# Supply.net
KiCad netlist of a schematic drawn in Altium Designer
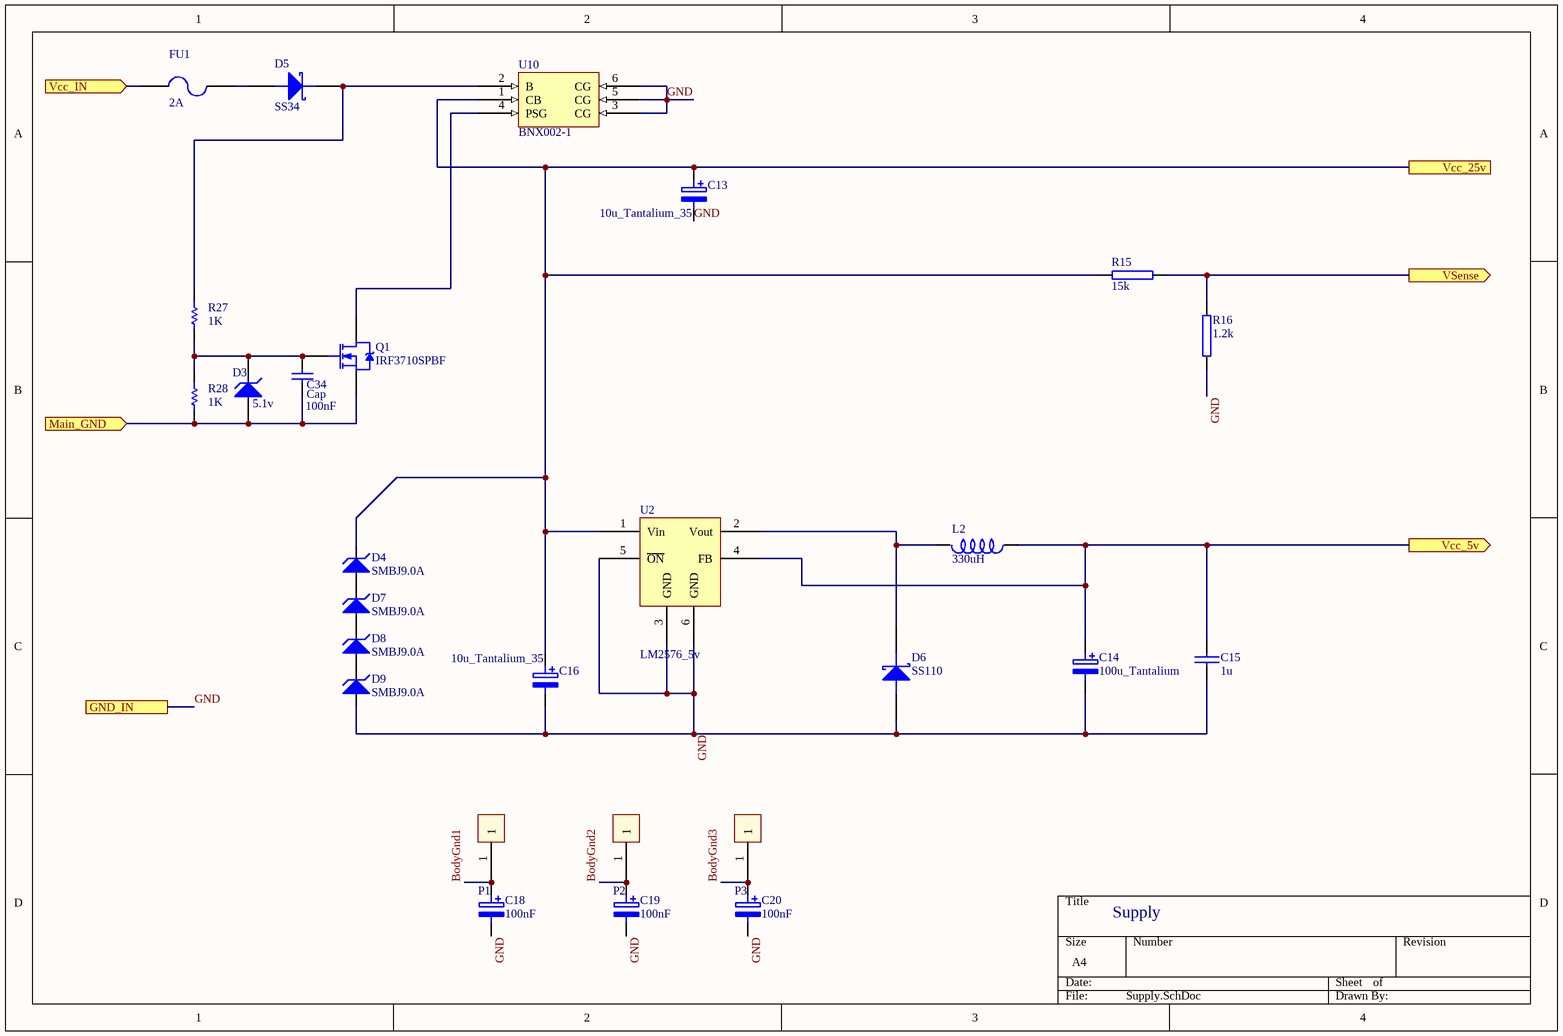
[diagram p0: Supply.SchDoc]

(export (version "E")
  (design (tool "Eeschema 10.0.6"))
  (components
    (comp (ref "C13")
      (value "10u_Tantalium_35")
      (footprint "Tantalum_9545")
      (libsource (lib "Sch_Lib_24") (part "CAP_ELECTRO"))
    )
    (comp (ref "C14")
      (value "100u_Tantalium")
      (footprint "Tantalum_9545")
      (libsource (lib "Miscellaneous Devices") (part "CAP_ELECTRO"))
    )
    (comp (ref "C15")
      (value "1u")
      (footprint "0805")
      (description "Capacitor")
      (libsource (lib "Sch_Lib_24") (part "CAP"))
    )
    (comp (ref "C16")
      (value "10u_Tantalium_35")
      (footprint "Tantalum_9545")
      (libsource (lib "Miscellaneous Devices") (part "CAP_ELECTRO"))
    )
    (comp (ref "C18")
      (value "100nF")
      (footprint "1206_SMD")
      (libsource (lib "Miscellaneous Devices") (part "CAP_ELECTRO"))
    )
    (comp (ref "C19")
      (value "100nF")
      (footprint "1206_SMD")
      (libsource (lib "Miscellaneous Devices") (part "CAP_ELECTRO"))
    )
    (comp (ref "C20")
      (value "100nF")
      (footprint "1206_SMD")
      (libsource (lib "Miscellaneous Devices") (part "CAP_ELECTRO"))
    )
    (comp (ref "C34")
      (value "Cap")
      (footprint "1206_SMD")
      (description "Capacitor")
      (fields (field (name "ALTIUM_VALUE") "100nF") (field (name "PUBLISHER") "Altium Limited"))
      (libsource (lib "Miscellaneous Devices") (part "Cap"))
    )
    (comp (ref "D3")
      (value "5.1v")
      (footprint "diode zener_smd")
      (description "Zener Diode")
      (fields (field (name "PUBLISHER") "Altium Limited"))
      (libsource (lib "Miscellaneous Devices") (part "D Zener"))
    )
    (comp (ref "D4") (value "SMBJ9.0A") (footprint "SMB") (libsource (lib "Sch_Lib_25") (part "ZENER")))
    (comp (ref "D5")
      (value "SS34")
      (footprint "SMC")
      (libsource (lib "Miscellaneous Devices") (part "DIODE_SCH"))
    )
    (comp (ref "D6") (value "SS110") (footprint "SMA") (libsource (lib "Sch_Lib_24") (part "DIODE_SCH")))
    (comp (ref "D7") (value "SMBJ9.0A") (footprint "SMB") (libsource (lib "Sch_Lib_25") (part "ZENER")))
    (comp (ref "D8") (value "SMBJ9.0A") (footprint "SMB") (libsource (lib "Sch_Lib_25") (part "ZENER")))
    (comp (ref "D9") (value "SMBJ9.0A") (footprint "SMB") (libsource (lib "Sch_Lib_25") (part "ZENER")))
    (comp (ref "FU1")
      (value "2A")
      (footprint "7227")
      (description "Fuse")
      (libsource (lib "Sch_Lib_24") (part "FUSE2"))
    )
    (comp (ref "L2")
      (value "330uH")
      (footprint "inductor_12.3*12.3")
      (libsource (lib "Miscellaneous Devices") (part "INDUCTOR"))
    )
    (comp (ref "P1") (value "head1") (footprint "PAD") (libsource (lib "CustomLib_Ver01") (part "head1")))
    (comp (ref "P2") (value "head1") (footprint "PAD") (libsource (lib "CustomLib_Ver01") (part "head1")))
    (comp (ref "P3") (value "head1") (footprint "PAD") (libsource (lib "CustomLib_Ver01") (part "head1")))
    (comp (ref "Q1")
      (value "IRF3710SPBF")
      (footprint "D2PAK")
      (description "N-Channel Power MOSFET")
      (fields (field (name "PUBLISHER") "Altium Limited"))
      (libsource (lib "Miscellaneous Devices") (part "NMOS-2"))
    )
    (comp (ref "R15") (value "15k") (footprint "1206_SMD") (libsource (lib "Sch_Lib_24") (part "RES2")))
    (comp (ref "R16") (value "1.2k") (footprint "1206_SMD") (libsource (lib "Sch_Lib_24") (part "RES2")))
    (comp (ref "R27")
      (value "1K")
      (footprint "0805_smd")
      (description "Resistor")
      (fields (field (name "Comment") "Res1") (field (name "PUBLISHER") "Altium Limited"))
      (libsource (lib "Miscellaneous Devices") (part "Res1"))
    )
    (comp (ref "R28")
      (value "1K")
      (footprint "0805")
      (description "Resistor")
      (fields (field (name "Comment") "Res1") (field (name "PUBLISHER") "Altium Limited"))
      (libsource (lib "Miscellaneous Devices") (part "Res1"))
    )
    (comp (ref "U2")
      (value "LM2576_5v")
      (footprint "TO263-5L")
      (libsource (lib "CustomLib_Ver01") (part "LM2576_5v"))
    )
    (comp (ref "U10")
      (value "BNX002-1")
      (footprint "BNX002-1")
      (description "EMI FILTERS")
      (libsource (lib "CustomLib_Ver01") (part "BNX002-1"))
    )
  )
  (nets
    (net (code "1") (name "/BodyGnd1") (class "Default")
      (node (ref "C18") (pin "1") (pintype "passive"))
      (node (ref "P1") (pin "1") (pinfunction "1_1") (pintype "passive"))
    )
    (net (code "2") (name "/BodyGnd2") (class "Default")
      (node (ref "C19") (pin "1") (pintype "passive"))
      (node (ref "P2") (pin "1") (pinfunction "1_1") (pintype "passive"))
    )
    (net (code "3") (name "/BodyGnd3") (class "Default")
      (node (ref "C20") (pin "1") (pintype "passive"))
      (node (ref "P3") (pin "1") (pinfunction "1_1") (pintype "passive"))
    )
    (net (code "4") (name "/GND") (class "Default")
      (node (ref "C13") (pin "2") (pintype "passive"))
      (node (ref "C14") (pin "2") (pintype "passive"))
      (node (ref "C15") (pin "2") (pinfunction "2_2") (pintype "passive"))
      (node (ref "C16") (pin "2") (pintype "passive"))
      (node (ref "C18") (pin "2") (pintype "passive"))
      (node (ref "C19") (pin "2") (pintype "passive"))
      (node (ref "C20") (pin "2") (pintype "passive"))
      (node (ref "D6") (pin "A") (pinfunction "A_A") (pintype "passive"))
      (node (ref "D9") (pin "A") (pintype "passive"))
      (node (ref "R16") (pin "1") (pintype "passive"))
      (node (ref "U10") (pin "3") (pinfunction "CG_3") (pintype "input"))
      (node (ref "U10") (pin "5") (pinfunction "CG_5") (pintype "input"))
      (node (ref "U10") (pin "6") (pinfunction "CG_6") (pintype "input"))
      (node (ref "U2") (pin "3") (pinfunction "GND_3") (pintype "passive"))
      (node (ref "U2") (pin "5") (pinfunction "~{ON}_5") (pintype "passive"))
      (node (ref "U2") (pin "6") (pinfunction "GND_6") (pintype "passive"))
    )
    (net (code "5") (name "/Main_GND") (class "Default")
      (node (ref "C34") (pin "1") (pinfunction "1_1") (pintype "passive"))
      (node (ref "D3") (pin "1") (pinfunction "A_1") (pintype "passive"))
      (node (ref "Q1") (pin "3") (pinfunction "S_3") (pintype "passive"))
      (node (ref "R28") (pin "1") (pinfunction "1_1") (pintype "passive"))
    )
    (net (code "6") (name "/VSense") (class "Default")
      (node (ref "R15") (pin "1") (pintype "passive"))
      (node (ref "R16") (pin "2") (pintype "passive"))
    )
    (net (code "7") (name "/Vcc_5v") (class "Default")
      (node (ref "C14") (pin "1") (pintype "passive"))
      (node (ref "C15") (pin "1") (pinfunction "1_1") (pintype "passive"))
      (node (ref "L2") (pin "1") (pintype "passive"))
      (node (ref "U2") (pin "4") (pinfunction "FB_4") (pintype "passive"))
    )
    (net (code "8") (name "/Vcc_25v") (class "Default")
      (node (ref "C13") (pin "1") (pintype "passive"))
      (node (ref "C16") (pin "1") (pintype "passive"))
      (node (ref "D4") (pin "K") (pintype "passive"))
      (node (ref "R15") (pin "2") (pintype "passive"))
      (node (ref "U10") (pin "1") (pinfunction "CB_1") (pintype "input"))
      (node (ref "U2") (pin "1") (pinfunction "Vin_1") (pintype "passive"))
    )
    (net (code "9") (name "/Vcc_IN") (class "Default")
      (node (ref "FU1") (pin "1") (pinfunction "1_1") (pintype "passive"))
    )
    (net (code "10") (name "Net-(D3-K)") (class "Default")
      (node (ref "C34") (pin "2") (pinfunction "2_2") (pintype "passive"))
      (node (ref "D3") (pin "2") (pinfunction "K_2") (pintype "passive"))
      (node (ref "Q1") (pin "1") (pinfunction "G_1") (pintype "passive"))
      (node (ref "R27") (pin "1") (pinfunction "1_1") (pintype "passive"))
      (node (ref "R28") (pin "2") (pinfunction "2_2") (pintype "passive"))
    )
    (net (code "11") (name "Net-(D4-PadA)") (class "Default")
      (node (ref "D4") (pin "A") (pintype "passive"))
      (node (ref "D7") (pin "K") (pintype "passive"))
    )
    (net (code "12") (name "Net-(D5-PadA)") (class "Default")
      (node (ref "D5") (pin "A") (pinfunction "A_A") (pintype "passive"))
      (node (ref "FU1") (pin "2") (pinfunction "2_2") (pintype "passive"))
    )
    (net (code "13") (name "Net-(D7-PadA)") (class "Default")
      (node (ref "D7") (pin "A") (pintype "passive"))
      (node (ref "D8") (pin "K") (pintype "passive"))
    )
    (net (code "14") (name "Net-(D8-PadA)") (class "Default")
      (node (ref "D8") (pin "A") (pintype "passive"))
      (node (ref "D9") (pin "K") (pintype "passive"))
    )
    (net (code "15") (name "Net-(Q1-D)") (class "Default")
      (node (ref "Q1") (pin "2") (pinfunction "D_2") (pintype "passive"))
      (node (ref "U10") (pin "4") (pinfunction "PSG_4") (pintype "input"))
    )
    (net (code "16") (name "Net-(U2-Vout)") (class "Default")
      (node (ref "D6") (pin "K") (pinfunction "K_K") (pintype "passive"))
      (node (ref "L2") (pin "2") (pintype "passive"))
      (node (ref "U2") (pin "2") (pinfunction "Vout_2") (pintype "passive"))
    )
    (net (code "17") (name "Net-(U10-B)") (class "Default")
      (node (ref "D5") (pin "K") (pinfunction "K_K") (pintype "passive"))
      (node (ref "R27") (pin "2") (pinfunction "2_2") (pintype "passive"))
      (node (ref "U10") (pin "2") (pinfunction "B_2") (pintype "input"))
    )
  )
)
